# untitled.net
KiCad netlist of a schematic drawn in EAGLE
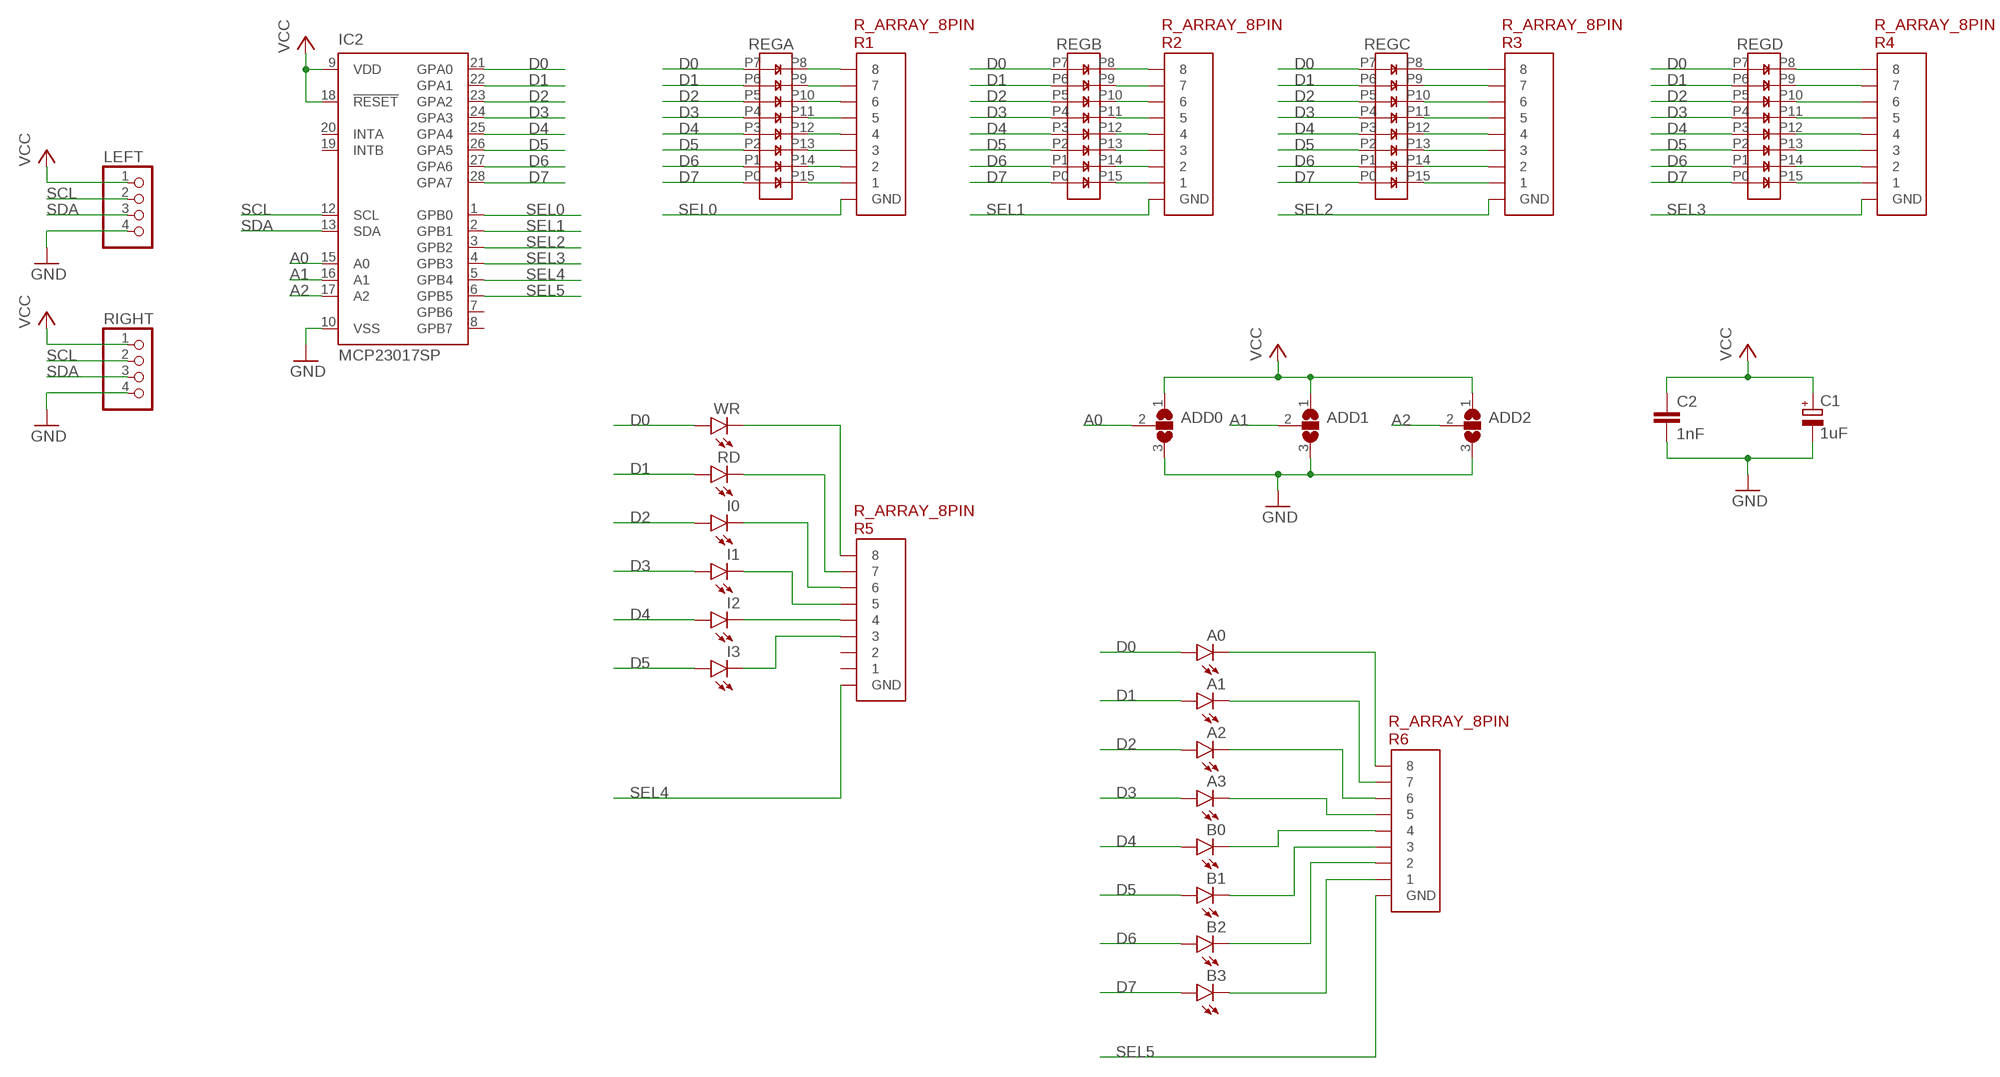
[diagram p0: schematic, sheet 1]

(export (version "E")
  (design (tool "Eeschema 10.0.6"))
  (components
    (comp (ref "A0")
      (value "LED3MM")
      (footprint "eagle-import:LED3MM")
      (libsource (lib "eagle-import") (part "LED3MM"))
    )
    (comp (ref "A1")
      (value "LED3MM")
      (footprint "eagle-import:LED3MM")
      (libsource (lib "eagle-import") (part "LED3MM"))
    )
    (comp (ref "A2")
      (value "LED3MM")
      (footprint "eagle-import:LED3MM")
      (libsource (lib "eagle-import") (part "LED3MM"))
    )
    (comp (ref "A3")
      (value "LED3MM")
      (footprint "eagle-import:LED3MM")
      (libsource (lib "eagle-import") (part "LED3MM"))
    )
    (comp (ref "ADD0")
      (value "SJ2W")
      (footprint "eagle-import:SJ_2")
      (libsource (lib "eagle-import") (part "SJ2W"))
    )
    (comp (ref "ADD1")
      (value "SJ2W")
      (footprint "eagle-import:SJ_2")
      (libsource (lib "eagle-import") (part "SJ2W"))
    )
    (comp (ref "ADD2")
      (value "SJ2W")
      (footprint "eagle-import:SJ_2")
      (libsource (lib "eagle-import") (part "SJ2W"))
    )
    (comp (ref "B0")
      (value "LED3MM")
      (footprint "eagle-import:LED3MM")
      (libsource (lib "eagle-import") (part "LED3MM"))
    )
    (comp (ref "B1")
      (value "LED3MM")
      (footprint "eagle-import:LED3MM")
      (libsource (lib "eagle-import") (part "LED3MM"))
    )
    (comp (ref "B2")
      (value "LED3MM")
      (footprint "eagle-import:LED3MM")
      (libsource (lib "eagle-import") (part "LED3MM"))
    )
    (comp (ref "B3")
      (value "LED3MM")
      (footprint "eagle-import:LED3MM")
      (libsource (lib "eagle-import") (part "LED3MM"))
    )
    (comp (ref "C1")
      (value "1uF")
      (footprint "eagle-import:E2,5-6")
      (libsource (lib "eagle-import") (part "CPOL-EUE2.5-6"))
    )
    (comp (ref "C2")
      (value "1nF")
      (footprint "eagle-import:C2.5-2")
      (libsource (lib "eagle-import") (part "C2.5/2"))
    )
    (comp (ref "I0")
      (value "LED3MM")
      (footprint "eagle-import:LED3MM")
      (libsource (lib "eagle-import") (part "LED3MM"))
    )
    (comp (ref "I1")
      (value "LED3MM")
      (footprint "eagle-import:LED3MM")
      (libsource (lib "eagle-import") (part "LED3MM"))
    )
    (comp (ref "I2")
      (value "LED3MM")
      (footprint "eagle-import:LED3MM")
      (libsource (lib "eagle-import") (part "LED3MM"))
    )
    (comp (ref "I3")
      (value "LED3MM")
      (footprint "eagle-import:LED3MM")
      (libsource (lib "eagle-import") (part "LED3MM"))
    )
    (comp (ref "IC2")
      (value "MCP23017SP")
      (footprint "eagle-import:DIL28-3")
      (fields (field (name "MF") "MICROCHIP") (field (name "MPN") "MCP23017-E/SP"))
      (libsource (lib "eagle-import") (part "MCP23017SP"))
    )
    (comp (ref "LEFT")
      (value "PINHD-1X4")
      (footprint "eagle-import:1X04")
      (libsource (lib "eagle-import") (part "PINHD-1X4"))
    )
    (comp (ref "R1")
      (value "R_ARRAY_8PIN")
      (footprint "eagle-import:R_ARRAY_8PIN")
      (libsource (lib "eagle-import") (part "R_ARRAY_8PIN"))
    )
    (comp (ref "R2")
      (value "R_ARRAY_8PIN")
      (footprint "eagle-import:R_ARRAY_8PIN")
      (libsource (lib "eagle-import") (part "R_ARRAY_8PIN"))
    )
    (comp (ref "R3")
      (value "R_ARRAY_8PIN")
      (footprint "eagle-import:R_ARRAY_8PIN")
      (libsource (lib "eagle-import") (part "R_ARRAY_8PIN"))
    )
    (comp (ref "R4")
      (value "R_ARRAY_8PIN")
      (footprint "eagle-import:R_ARRAY_8PIN")
      (libsource (lib "eagle-import") (part "R_ARRAY_8PIN"))
    )
    (comp (ref "R5")
      (value "R_ARRAY_8PIN")
      (footprint "eagle-import:R_ARRAY_8PIN")
      (libsource (lib "eagle-import") (part "R_ARRAY_8PIN"))
    )
    (comp (ref "R6")
      (value "R_ARRAY_8PIN")
      (footprint "eagle-import:R_ARRAY_8PIN")
      (libsource (lib "eagle-import") (part "R_ARRAY_8PIN"))
    )
    (comp (ref "RD")
      (value "LED3MM")
      (footprint "eagle-import:LED3MM")
      (libsource (lib "eagle-import") (part "LED3MM"))
    )
    (comp (ref "REGA")
      (value "LB8")
      (footprint "eagle-import:LB8")
      (libsource (lib "eagle-import") (part "LB8"))
    )
    (comp (ref "REGB")
      (value "LB8")
      (footprint "eagle-import:LB8")
      (libsource (lib "eagle-import") (part "LB8"))
    )
    (comp (ref "REGC")
      (value "LB8")
      (footprint "eagle-import:LB8")
      (libsource (lib "eagle-import") (part "LB8"))
    )
    (comp (ref "REGD")
      (value "LB8")
      (footprint "eagle-import:LB8")
      (libsource (lib "eagle-import") (part "LB8"))
    )
    (comp (ref "RIGHT")
      (value "PINHD-1X4")
      (footprint "eagle-import:1X04")
      (libsource (lib "eagle-import") (part "PINHD-1X4"))
    )
    (comp (ref "WR")
      (value "LED3MM")
      (footprint "eagle-import:LED3MM")
      (libsource (lib "eagle-import") (part "LED3MM"))
    )
  )
  (nets
    (net (code "1") (name "/A0") (class "Default")
      (node (ref "ADD0") (pin "2") (pinfunction "2_2") (pintype "passive"))
      (node (ref "IC2") (pin "15") (pinfunction "A0_15") (pintype "input"))
    )
    (net (code "2") (name "/A1") (class "Default")
      (node (ref "ADD1") (pin "2") (pinfunction "2_2") (pintype "passive"))
      (node (ref "IC2") (pin "16") (pinfunction "A1_16") (pintype "input"))
    )
    (net (code "3") (name "/A2") (class "Default")
      (node (ref "ADD2") (pin "2") (pinfunction "2_2") (pintype "passive"))
      (node (ref "IC2") (pin "17") (pinfunction "A2_17") (pintype "input"))
    )
    (net (code "4") (name "/D0") (class "Default")
      (node (ref "A0") (pin "A") (pinfunction "A_A") (pintype "passive"))
      (node (ref "IC2") (pin "21") (pinfunction "GPA0_21") (pintype "bidirectional"))
      (node (ref "REGA") (pin "P7") (pinfunction "P7_P7") (pintype "bidirectional"))
      (node (ref "REGB") (pin "P7") (pinfunction "P7_P7") (pintype "bidirectional"))
      (node (ref "REGC") (pin "P7") (pinfunction "P7_P7") (pintype "bidirectional"))
      (node (ref "REGD") (pin "P7") (pinfunction "P7_P7") (pintype "bidirectional"))
      (node (ref "WR") (pin "A") (pinfunction "A_A") (pintype "passive"))
    )
    (net (code "5") (name "/D1") (class "Default")
      (node (ref "A1") (pin "A") (pinfunction "A_A") (pintype "passive"))
      (node (ref "IC2") (pin "22") (pinfunction "GPA1_22") (pintype "bidirectional"))
      (node (ref "RD") (pin "A") (pinfunction "A_A") (pintype "passive"))
      (node (ref "REGA") (pin "P6") (pinfunction "P6_P6") (pintype "bidirectional"))
      (node (ref "REGB") (pin "P6") (pinfunction "P6_P6") (pintype "bidirectional"))
      (node (ref "REGC") (pin "P6") (pinfunction "P6_P6") (pintype "bidirectional"))
      (node (ref "REGD") (pin "P6") (pinfunction "P6_P6") (pintype "bidirectional"))
    )
    (net (code "6") (name "/D2") (class "Default")
      (node (ref "A2") (pin "A") (pinfunction "A_A") (pintype "passive"))
      (node (ref "I0") (pin "A") (pinfunction "A_A") (pintype "passive"))
      (node (ref "IC2") (pin "23") (pinfunction "GPA2_23") (pintype "bidirectional"))
      (node (ref "REGA") (pin "P5") (pinfunction "P5_P5") (pintype "bidirectional"))
      (node (ref "REGB") (pin "P5") (pinfunction "P5_P5") (pintype "bidirectional"))
      (node (ref "REGC") (pin "P5") (pinfunction "P5_P5") (pintype "bidirectional"))
      (node (ref "REGD") (pin "P5") (pinfunction "P5_P5") (pintype "bidirectional"))
    )
    (net (code "7") (name "/D3") (class "Default")
      (node (ref "A3") (pin "A") (pinfunction "A_A") (pintype "passive"))
      (node (ref "I1") (pin "A") (pinfunction "A_A") (pintype "passive"))
      (node (ref "IC2") (pin "24") (pinfunction "GPA3_24") (pintype "bidirectional"))
      (node (ref "REGA") (pin "P4") (pinfunction "P4_P4") (pintype "bidirectional"))
      (node (ref "REGB") (pin "P4") (pinfunction "P4_P4") (pintype "bidirectional"))
      (node (ref "REGC") (pin "P4") (pinfunction "P4_P4") (pintype "bidirectional"))
      (node (ref "REGD") (pin "P4") (pinfunction "P4_P4") (pintype "bidirectional"))
    )
    (net (code "8") (name "/D4") (class "Default")
      (node (ref "B0") (pin "A") (pinfunction "A_A") (pintype "passive"))
      (node (ref "I2") (pin "A") (pinfunction "A_A") (pintype "passive"))
      (node (ref "IC2") (pin "25") (pinfunction "GPA4_25") (pintype "bidirectional"))
      (node (ref "REGA") (pin "P3") (pinfunction "P3_P3") (pintype "bidirectional"))
      (node (ref "REGB") (pin "P3") (pinfunction "P3_P3") (pintype "bidirectional"))
      (node (ref "REGC") (pin "P3") (pinfunction "P3_P3") (pintype "bidirectional"))
      (node (ref "REGD") (pin "P3") (pinfunction "P3_P3") (pintype "bidirectional"))
    )
    (net (code "9") (name "/D5") (class "Default")
      (node (ref "B1") (pin "A") (pinfunction "A_A") (pintype "passive"))
      (node (ref "I3") (pin "A") (pinfunction "A_A") (pintype "passive"))
      (node (ref "IC2") (pin "26") (pinfunction "GPA5_26") (pintype "bidirectional"))
      (node (ref "REGA") (pin "P2") (pinfunction "P2_P2") (pintype "bidirectional"))
      (node (ref "REGB") (pin "P2") (pinfunction "P2_P2") (pintype "bidirectional"))
      (node (ref "REGC") (pin "P2") (pinfunction "P2_P2") (pintype "bidirectional"))
      (node (ref "REGD") (pin "P2") (pinfunction "P2_P2") (pintype "bidirectional"))
    )
    (net (code "10") (name "/D6") (class "Default")
      (node (ref "B2") (pin "A") (pinfunction "A_A") (pintype "passive"))
      (node (ref "IC2") (pin "27") (pinfunction "GPA6_27") (pintype "bidirectional"))
      (node (ref "REGA") (pin "P1") (pinfunction "P1_P1") (pintype "bidirectional"))
      (node (ref "REGB") (pin "P1") (pinfunction "P1_P1") (pintype "bidirectional"))
      (node (ref "REGC") (pin "P1") (pinfunction "P1_P1") (pintype "bidirectional"))
      (node (ref "REGD") (pin "P1") (pinfunction "P1_P1") (pintype "bidirectional"))
    )
    (net (code "11") (name "/D7") (class "Default")
      (node (ref "B3") (pin "A") (pinfunction "A_A") (pintype "passive"))
      (node (ref "IC2") (pin "28") (pinfunction "GPA7_28") (pintype "bidirectional"))
      (node (ref "REGA") (pin "P0") (pinfunction "P0_P0") (pintype "bidirectional"))
      (node (ref "REGB") (pin "P0") (pinfunction "P0_P0") (pintype "bidirectional"))
      (node (ref "REGC") (pin "P0") (pinfunction "P0_P0") (pintype "bidirectional"))
      (node (ref "REGD") (pin "P0") (pinfunction "P0_P0") (pintype "bidirectional"))
    )
    (net (code "12") (name "/SCL") (class "Default")
      (node (ref "IC2") (pin "12") (pinfunction "SCL_12") (pintype "input"))
      (node (ref "LEFT") (pin "2") (pinfunction "2_2") (pintype "passive"))
      (node (ref "RIGHT") (pin "2") (pinfunction "2_2") (pintype "passive"))
    )
    (net (code "13") (name "/SDA") (class "Default")
      (node (ref "IC2") (pin "13") (pinfunction "SDA_13") (pintype "bidirectional"))
      (node (ref "LEFT") (pin "3") (pinfunction "3_3") (pintype "passive"))
      (node (ref "RIGHT") (pin "3") (pinfunction "3_3") (pintype "passive"))
    )
    (net (code "14") (name "/SEL0") (class "Default")
      (node (ref "IC2") (pin "1") (pinfunction "GPB0_1") (pintype "bidirectional"))
      (node (ref "R1") (pin "GND") (pinfunction "GND_GND") (pintype "bidirectional"))
    )
    (net (code "15") (name "/SEL1") (class "Default")
      (node (ref "IC2") (pin "2") (pinfunction "GPB1_2") (pintype "bidirectional"))
      (node (ref "R2") (pin "GND") (pinfunction "GND_GND") (pintype "bidirectional"))
    )
    (net (code "16") (name "/SEL2") (class "Default")
      (node (ref "IC2") (pin "3") (pinfunction "GPB2_3") (pintype "bidirectional"))
      (node (ref "R3") (pin "GND") (pinfunction "GND_GND") (pintype "bidirectional"))
    )
    (net (code "17") (name "/SEL3") (class "Default")
      (node (ref "IC2") (pin "4") (pinfunction "GPB3_4") (pintype "bidirectional"))
      (node (ref "R4") (pin "GND") (pinfunction "GND_GND") (pintype "bidirectional"))
    )
    (net (code "18") (name "/SEL4") (class "Default")
      (node (ref "IC2") (pin "5") (pinfunction "GPB4_5") (pintype "bidirectional"))
      (node (ref "R5") (pin "GND") (pinfunction "GND_GND") (pintype "bidirectional"))
    )
    (net (code "19") (name "/SEL5") (class "Default")
      (node (ref "IC2") (pin "6") (pinfunction "GPB5_6") (pintype "bidirectional"))
      (node (ref "R6") (pin "GND") (pinfunction "GND_GND") (pintype "bidirectional"))
    )
    (net (code "20") (name "GND") (class "Default")
      (node (ref "ADD0") (pin "3") (pinfunction "3_3") (pintype "passive"))
      (node (ref "ADD1") (pin "3") (pinfunction "3_3") (pintype "passive"))
      (node (ref "ADD2") (pin "3") (pinfunction "3_3") (pintype "passive"))
      (node (ref "C1") (pin "-") (pinfunction "-_-") (pintype "passive"))
      (node (ref "C2") (pin "2") (pinfunction "2_2") (pintype "passive"))
      (node (ref "IC2") (pin "10") (pinfunction "VSS_10") (pintype "power_in"))
      (node (ref "LEFT") (pin "4") (pinfunction "4_4") (pintype "passive"))
      (node (ref "RIGHT") (pin "4") (pinfunction "4_4") (pintype "passive"))
    )
    (net (code "21") (name "Net-(A0-C)") (class "Default")
      (node (ref "A0") (pin "K") (pinfunction "C_K") (pintype "passive"))
      (node (ref "R6") (pin "8") (pinfunction "8_8") (pintype "bidirectional"))
    )
    (net (code "22") (name "Net-(A1-C)") (class "Default")
      (node (ref "A1") (pin "K") (pinfunction "C_K") (pintype "passive"))
      (node (ref "R6") (pin "7") (pinfunction "7_7") (pintype "bidirectional"))
    )
    (net (code "23") (name "Net-(A2-C)") (class "Default")
      (node (ref "A2") (pin "K") (pinfunction "C_K") (pintype "passive"))
      (node (ref "R6") (pin "6") (pinfunction "6_6") (pintype "bidirectional"))
    )
    (net (code "24") (name "Net-(A3-C)") (class "Default")
      (node (ref "A3") (pin "K") (pinfunction "C_K") (pintype "passive"))
      (node (ref "R6") (pin "5") (pinfunction "5_5") (pintype "bidirectional"))
    )
    (net (code "25") (name "Net-(B0-C)") (class "Default")
      (node (ref "B0") (pin "K") (pinfunction "C_K") (pintype "passive"))
      (node (ref "R6") (pin "4") (pinfunction "4_4") (pintype "bidirectional"))
    )
    (net (code "26") (name "Net-(B1-C)") (class "Default")
      (node (ref "B1") (pin "K") (pinfunction "C_K") (pintype "passive"))
      (node (ref "R6") (pin "3") (pinfunction "3_3") (pintype "bidirectional"))
    )
    (net (code "27") (name "Net-(B2-C)") (class "Default")
      (node (ref "B2") (pin "K") (pinfunction "C_K") (pintype "passive"))
      (node (ref "R6") (pin "2") (pinfunction "2_2") (pintype "bidirectional"))
    )
    (net (code "28") (name "Net-(B3-C)") (class "Default")
      (node (ref "B3") (pin "K") (pinfunction "C_K") (pintype "passive"))
      (node (ref "R6") (pin "1") (pinfunction "1_1") (pintype "bidirectional"))
    )
    (net (code "29") (name "Net-(I0-C)") (class "Default")
      (node (ref "I0") (pin "K") (pinfunction "C_K") (pintype "passive"))
      (node (ref "R5") (pin "6") (pinfunction "6_6") (pintype "bidirectional"))
    )
    (net (code "30") (name "Net-(I1-C)") (class "Default")
      (node (ref "I1") (pin "K") (pinfunction "C_K") (pintype "passive"))
      (node (ref "R5") (pin "5") (pinfunction "5_5") (pintype "bidirectional"))
    )
    (net (code "31") (name "Net-(I2-C)") (class "Default")
      (node (ref "I2") (pin "K") (pinfunction "C_K") (pintype "passive"))
      (node (ref "R5") (pin "4") (pinfunction "4_4") (pintype "bidirectional"))
    )
    (net (code "32") (name "Net-(I3-C)") (class "Default")
      (node (ref "I3") (pin "K") (pinfunction "C_K") (pintype "passive"))
      (node (ref "R5") (pin "3") (pinfunction "3_3") (pintype "bidirectional"))
    )
    (net (code "33") (name "Net-(R1-Pad1)") (class "Default")
      (node (ref "R1") (pin "1") (pinfunction "1_1") (pintype "bidirectional"))
      (node (ref "REGA") (pin "P15") (pinfunction "P15_P15") (pintype "bidirectional"))
    )
    (net (code "34") (name "Net-(R1-Pad2)") (class "Default")
      (node (ref "R1") (pin "2") (pinfunction "2_2") (pintype "bidirectional"))
      (node (ref "REGA") (pin "P14") (pinfunction "P14_P14") (pintype "bidirectional"))
    )
    (net (code "35") (name "Net-(R1-Pad3)") (class "Default")
      (node (ref "R1") (pin "3") (pinfunction "3_3") (pintype "bidirectional"))
      (node (ref "REGA") (pin "P13") (pinfunction "P13_P13") (pintype "bidirectional"))
    )
    (net (code "36") (name "Net-(R1-Pad4)") (class "Default")
      (node (ref "R1") (pin "4") (pinfunction "4_4") (pintype "bidirectional"))
      (node (ref "REGA") (pin "P12") (pinfunction "P12_P12") (pintype "bidirectional"))
    )
    (net (code "37") (name "Net-(R1-Pad5)") (class "Default")
      (node (ref "R1") (pin "5") (pinfunction "5_5") (pintype "bidirectional"))
      (node (ref "REGA") (pin "P11") (pinfunction "P11_P11") (pintype "bidirectional"))
    )
    (net (code "38") (name "Net-(R1-Pad6)") (class "Default")
      (node (ref "R1") (pin "6") (pinfunction "6_6") (pintype "bidirectional"))
      (node (ref "REGA") (pin "P10") (pinfunction "P10_P10") (pintype "bidirectional"))
    )
    (net (code "39") (name "Net-(R1-Pad7)") (class "Default")
      (node (ref "R1") (pin "7") (pinfunction "7_7") (pintype "bidirectional"))
      (node (ref "REGA") (pin "P9") (pinfunction "P9_P9") (pintype "bidirectional"))
    )
    (net (code "40") (name "Net-(R1-Pad8)") (class "Default")
      (node (ref "R1") (pin "8") (pinfunction "8_8") (pintype "bidirectional"))
      (node (ref "REGA") (pin "P8") (pinfunction "P8_P8") (pintype "bidirectional"))
    )
    (net (code "41") (name "Net-(R2-Pad1)") (class "Default")
      (node (ref "R2") (pin "1") (pinfunction "1_1") (pintype "bidirectional"))
      (node (ref "REGB") (pin "P15") (pinfunction "P15_P15") (pintype "bidirectional"))
    )
    (net (code "42") (name "Net-(R2-Pad2)") (class "Default")
      (node (ref "R2") (pin "2") (pinfunction "2_2") (pintype "bidirectional"))
      (node (ref "REGB") (pin "P14") (pinfunction "P14_P14") (pintype "bidirectional"))
    )
    (net (code "43") (name "Net-(R2-Pad3)") (class "Default")
      (node (ref "R2") (pin "3") (pinfunction "3_3") (pintype "bidirectional"))
      (node (ref "REGB") (pin "P13") (pinfunction "P13_P13") (pintype "bidirectional"))
    )
    (net (code "44") (name "Net-(R2-Pad4)") (class "Default")
      (node (ref "R2") (pin "4") (pinfunction "4_4") (pintype "bidirectional"))
      (node (ref "REGB") (pin "P12") (pinfunction "P12_P12") (pintype "bidirectional"))
    )
    (net (code "45") (name "Net-(R2-Pad5)") (class "Default")
      (node (ref "R2") (pin "5") (pinfunction "5_5") (pintype "bidirectional"))
      (node (ref "REGB") (pin "P11") (pinfunction "P11_P11") (pintype "bidirectional"))
    )
    (net (code "46") (name "Net-(R2-Pad6)") (class "Default")
      (node (ref "R2") (pin "6") (pinfunction "6_6") (pintype "bidirectional"))
      (node (ref "REGB") (pin "P10") (pinfunction "P10_P10") (pintype "bidirectional"))
    )
    (net (code "47") (name "Net-(R2-Pad7)") (class "Default")
      (node (ref "R2") (pin "7") (pinfunction "7_7") (pintype "bidirectional"))
      (node (ref "REGB") (pin "P9") (pinfunction "P9_P9") (pintype "bidirectional"))
    )
    (net (code "48") (name "Net-(R2-Pad8)") (class "Default")
      (node (ref "R2") (pin "8") (pinfunction "8_8") (pintype "bidirectional"))
      (node (ref "REGB") (pin "P8") (pinfunction "P8_P8") (pintype "bidirectional"))
    )
    (net (code "49") (name "Net-(R3-Pad1)") (class "Default")
      (node (ref "R3") (pin "1") (pinfunction "1_1") (pintype "bidirectional"))
      (node (ref "REGC") (pin "P15") (pinfunction "P15_P15") (pintype "bidirectional"))
    )
    (net (code "50") (name "Net-(R3-Pad2)") (class "Default")
      (node (ref "R3") (pin "2") (pinfunction "2_2") (pintype "bidirectional"))
      (node (ref "REGC") (pin "P14") (pinfunction "P14_P14") (pintype "bidirectional"))
    )
    (net (code "51") (name "Net-(R3-Pad3)") (class "Default")
      (node (ref "R3") (pin "3") (pinfunction "3_3") (pintype "bidirectional"))
      (node (ref "REGC") (pin "P13") (pinfunction "P13_P13") (pintype "bidirectional"))
    )
    (net (code "52") (name "Net-(R3-Pad4)") (class "Default")
      (node (ref "R3") (pin "4") (pinfunction "4_4") (pintype "bidirectional"))
      (node (ref "REGC") (pin "P12") (pinfunction "P12_P12") (pintype "bidirectional"))
    )
    (net (code "53") (name "Net-(R3-Pad5)") (class "Default")
      (node (ref "R3") (pin "5") (pinfunction "5_5") (pintype "bidirectional"))
      (node (ref "REGC") (pin "P11") (pinfunction "P11_P11") (pintype "bidirectional"))
    )
    (net (code "54") (name "Net-(R3-Pad6)") (class "Default")
      (node (ref "R3") (pin "6") (pinfunction "6_6") (pintype "bidirectional"))
      (node (ref "REGC") (pin "P10") (pinfunction "P10_P10") (pintype "bidirectional"))
    )
    (net (code "55") (name "Net-(R3-Pad7)") (class "Default")
      (node (ref "R3") (pin "7") (pinfunction "7_7") (pintype "bidirectional"))
      (node (ref "REGC") (pin "P9") (pinfunction "P9_P9") (pintype "bidirectional"))
    )
    (net (code "56") (name "Net-(R3-Pad8)") (class "Default")
      (node (ref "R3") (pin "8") (pinfunction "8_8") (pintype "bidirectional"))
      (node (ref "REGC") (pin "P8") (pinfunction "P8_P8") (pintype "bidirectional"))
    )
    (net (code "57") (name "Net-(R4-Pad1)") (class "Default")
      (node (ref "R4") (pin "1") (pinfunction "1_1") (pintype "bidirectional"))
      (node (ref "REGD") (pin "P15") (pinfunction "P15_P15") (pintype "bidirectional"))
    )
    (net (code "58") (name "Net-(R4-Pad2)") (class "Default")
      (node (ref "R4") (pin "2") (pinfunction "2_2") (pintype "bidirectional"))
      (node (ref "REGD") (pin "P14") (pinfunction "P14_P14") (pintype "bidirectional"))
    )
    (net (code "59") (name "Net-(R4-Pad3)") (class "Default")
      (node (ref "R4") (pin "3") (pinfunction "3_3") (pintype "bidirectional"))
      (node (ref "REGD") (pin "P13") (pinfunction "P13_P13") (pintype "bidirectional"))
    )
    (net (code "60") (name "Net-(R4-Pad4)") (class "Default")
      (node (ref "R4") (pin "4") (pinfunction "4_4") (pintype "bidirectional"))
      (node (ref "REGD") (pin "P12") (pinfunction "P12_P12") (pintype "bidirectional"))
    )
    (net (code "61") (name "Net-(R4-Pad5)") (class "Default")
      (node (ref "R4") (pin "5") (pinfunction "5_5") (pintype "bidirectional"))
      (node (ref "REGD") (pin "P11") (pinfunction "P11_P11") (pintype "bidirectional"))
    )
    (net (code "62") (name "Net-(R4-Pad6)") (class "Default")
      (node (ref "R4") (pin "6") (pinfunction "6_6") (pintype "bidirectional"))
      (node (ref "REGD") (pin "P10") (pinfunction "P10_P10") (pintype "bidirectional"))
    )
    (net (code "63") (name "Net-(R4-Pad7)") (class "Default")
      (node (ref "R4") (pin "7") (pinfunction "7_7") (pintype "bidirectional"))
      (node (ref "REGD") (pin "P9") (pinfunction "P9_P9") (pintype "bidirectional"))
    )
    (net (code "64") (name "Net-(R4-Pad8)") (class "Default")
      (node (ref "R4") (pin "8") (pinfunction "8_8") (pintype "bidirectional"))
      (node (ref "REGD") (pin "P8") (pinfunction "P8_P8") (pintype "bidirectional"))
    )
    (net (code "65") (name "Net-(RD-C)") (class "Default")
      (node (ref "R5") (pin "7") (pinfunction "7_7") (pintype "bidirectional"))
      (node (ref "RD") (pin "K") (pinfunction "C_K") (pintype "passive"))
    )
    (net (code "66") (name "Net-(WR-C)") (class "Default")
      (node (ref "R5") (pin "8") (pinfunction "8_8") (pintype "bidirectional"))
      (node (ref "WR") (pin "K") (pinfunction "C_K") (pintype "passive"))
    )
    (net (code "67") (name "VCC") (class "Default")
      (node (ref "ADD0") (pin "1") (pinfunction "1_1") (pintype "passive"))
      (node (ref "ADD1") (pin "1") (pinfunction "1_1") (pintype "passive"))
      (node (ref "ADD2") (pin "1") (pinfunction "1_1") (pintype "passive"))
      (node (ref "C1") (pin "+") (pinfunction "+_+") (pintype "passive"))
      (node (ref "C2") (pin "1") (pinfunction "1_1") (pintype "passive"))
      (node (ref "IC2") (pin "18") (pinfunction "~{RESET}_18") (pintype "input"))
      (node (ref "IC2") (pin "9") (pinfunction "VDD_9") (pintype "power_in"))
      (node (ref "LEFT") (pin "1") (pinfunction "1_1") (pintype "passive"))
      (node (ref "RIGHT") (pin "1") (pinfunction "1_1") (pintype "passive"))
    )
    (net (code "68") (name "unconnected-(IC2-GPB6-Pad7)") (class "Default")
      (node (ref "IC2") (pin "7") (pinfunction "GPB6_7") (pintype "bidirectional"))
    )
    (net (code "69") (name "unconnected-(IC2-GPB7-Pad8)") (class "Default")
      (node (ref "IC2") (pin "8") (pinfunction "GPB7_8") (pintype "bidirectional"))
    )
    (net (code "70") (name "unconnected-(IC2-INTA-Pad20)") (class "Default")
      (node (ref "IC2") (pin "20") (pinfunction "INTA_20") (pintype "output"))
    )
    (net (code "71") (name "unconnected-(IC2-INTB-Pad19)") (class "Default")
      (node (ref "IC2") (pin "19") (pinfunction "INTB_19") (pintype "output"))
    )
    (net (code "72") (name "unconnected-(R5-Pad1)") (class "Default")
      (node (ref "R5") (pin "1") (pinfunction "1_1") (pintype "bidirectional"))
    )
    (net (code "73") (name "unconnected-(R5-Pad2)") (class "Default")
      (node (ref "R5") (pin "2") (pinfunction "2_2") (pintype "bidirectional"))
    )
  )
)
